# esp01.net
KiCad netlist of a schematic drawn in EAGLE
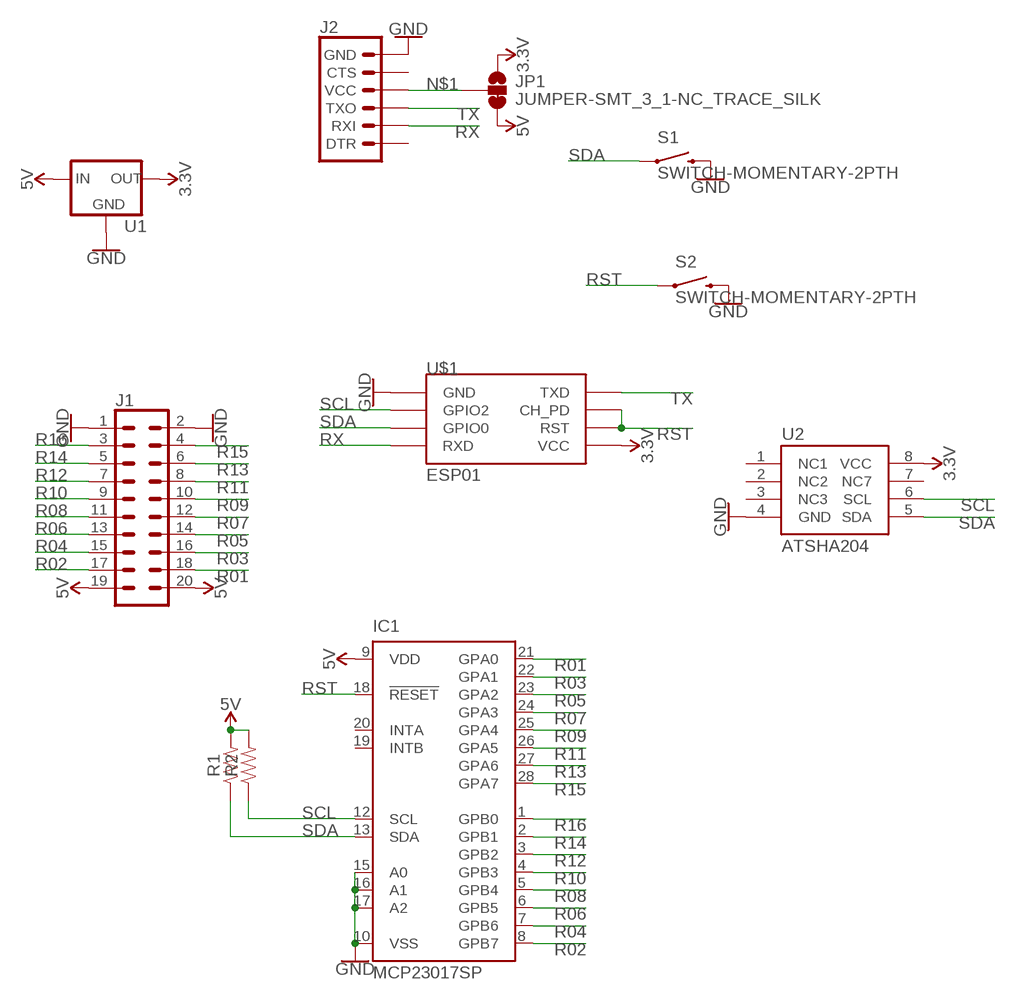
[diagram p0: schematic, sheet 1]

(export (version "E")
  (design (tool "Eeschema 10.0.6"))
  (components
    (comp (ref "IC1")
      (value "MCP23017SP")
      (footprint "eagle-import:DIL28-3")
      (libsource (lib "eagle-import") (part "MCP23017SP"))
    )
    (comp (ref "J1")
      (value "CONN_10X2")
      (footprint "eagle-import:2X10")
      (libsource (lib "eagle-import") (part "CONN_10X2"))
    )
    (comp (ref "J2")
      (value "6_PIN_SERIAL_TARGETLONGPADS")
      (footprint "eagle-import:1X06_LONGPADS")
      (libsource (lib "eagle-import") (part "6_PIN_SERIAL_TARGETLONGPADS"))
    )
    (comp (ref "JP1")
      (value "JUMPER-SMT_3_1-NC_TRACE_SILK")
      (footprint "eagle-import:SMT-JUMPER_3_1-NC_TRACE_SILK")
      (libsource (lib "eagle-import") (part "JUMPER-SMT_3_1-NC_TRACE_SILK"))
    )
    (comp (ref "R1")
      (value "RESISTORAXIAL-0.3")
      (footprint "eagle-import:AXIAL-0.3")
      (libsource (lib "eagle-import") (part "RESISTORAXIAL-0.3"))
    )
    (comp (ref "R2")
      (value "RESISTORAXIAL-0.3")
      (footprint "eagle-import:AXIAL-0.3")
      (libsource (lib "eagle-import") (part "RESISTORAXIAL-0.3"))
    )
    (comp (ref "S1")
      (value "SWITCH-MOMENTARY-2PTH")
      (footprint "eagle-import:TACTILE-PTH")
      (libsource (lib "eagle-import") (part "SWITCH-MOMENTARY-2PTH"))
    )
    (comp (ref "S2")
      (value "SWITCH-MOMENTARY-2PTH")
      (footprint "eagle-import:TACTILE-PTH")
      (libsource (lib "eagle-import") (part "SWITCH-MOMENTARY-2PTH"))
    )
    (comp (ref "U$1")
      (value "ESP01")
      (footprint "eagle-import:ESP01")
      (libsource (lib "eagle-import") (part "ESP01"))
    )
    (comp (ref "U1")
      (value "V_REG_78XXSIDE")
      (footprint "eagle-import:78XXL")
      (libsource (lib "eagle-import") (part "V_REG_78XXSIDE"))
    )
    (comp (ref "U2")
      (value "ATSHA204")
      (footprint "eagle-import:SO08")
      (libsource (lib "eagle-import") (part "ATSHA204_SOIC8"))
    )
  )
  (nets
    (net (code "1") (name "3.3V") (class "Default")
      (node (ref "JP1") (pin "1") (pinfunction "1_1") (pintype "passive"))
      (node (ref "U$1") (pin "VCC") (pinfunction "VCC_VCC") (pintype "bidirectional"))
      (node (ref "U1") (pin "OUT") (pinfunction "OUT_OUT") (pintype "passive"))
      (node (ref "U2") (pin "8") (pinfunction "VCC_8") (pintype "power_in"))
    )
    (net (code "2") (name "5V") (class "Default")
      (node (ref "IC1") (pin "9") (pinfunction "VDD_9") (pintype "power_in"))
      (node (ref "J1") (pin "19") (pinfunction "19_19") (pintype "passive"))
      (node (ref "J1") (pin "20") (pinfunction "20_20") (pintype "passive"))
      (node (ref "JP1") (pin "3") (pinfunction "3_3") (pintype "passive"))
      (node (ref "R1") (pin "P$2") (pinfunction "2_P$2") (pintype "passive"))
      (node (ref "R2") (pin "P$2") (pinfunction "2_P$2") (pintype "passive"))
      (node (ref "U1") (pin "IN") (pinfunction "IN_IN") (pintype "input"))
    )
    (net (code "3") (name "GND") (class "Default")
      (node (ref "IC1") (pin "10") (pinfunction "VSS_10") (pintype "power_in"))
      (node (ref "IC1") (pin "15") (pinfunction "A0_15") (pintype "input"))
      (node (ref "IC1") (pin "16") (pinfunction "A1_16") (pintype "input"))
      (node (ref "IC1") (pin "17") (pinfunction "A2_17") (pintype "input"))
      (node (ref "J1") (pin "1") (pinfunction "1_1") (pintype "passive"))
      (node (ref "J1") (pin "2") (pinfunction "2_2") (pintype "passive"))
      (node (ref "J2") (pin "6") (pinfunction "GND_6") (pintype "passive"))
      (node (ref "S1") (pin "3") (pinfunction "2_3") (pintype "passive"))
      (node (ref "S1") (pin "4") (pinfunction "2_4") (pintype "passive"))
      (node (ref "S2") (pin "3") (pinfunction "2_3") (pintype "passive"))
      (node (ref "S2") (pin "4") (pinfunction "2_4") (pintype "passive"))
      (node (ref "U$1") (pin "GND") (pinfunction "GND_GND") (pintype "bidirectional"))
      (node (ref "U1") (pin "GND") (pinfunction "GND_GND") (pintype "input"))
      (node (ref "U2") (pin "4") (pinfunction "GND_4") (pintype "power_in"))
    )
    (net (code "4") (name "N$1") (class "Default")
      (node (ref "J2") (pin "4") (pinfunction "VCC_4") (pintype "passive"))
      (node (ref "JP1") (pin "2") (pinfunction "2_2") (pintype "passive"))
    )
    (net (code "5") (name "R01") (class "Default")
      (node (ref "IC1") (pin "21") (pinfunction "GPA0_21") (pintype "bidirectional"))
      (node (ref "J1") (pin "18") (pinfunction "18_18") (pintype "passive"))
    )
    (net (code "6") (name "R02") (class "Default")
      (node (ref "IC1") (pin "8") (pinfunction "GPB7_8") (pintype "bidirectional"))
      (node (ref "J1") (pin "17") (pinfunction "17_17") (pintype "passive"))
    )
    (net (code "7") (name "R03") (class "Default")
      (node (ref "IC1") (pin "22") (pinfunction "GPA1_22") (pintype "bidirectional"))
      (node (ref "J1") (pin "16") (pinfunction "16_16") (pintype "passive"))
    )
    (net (code "8") (name "R04") (class "Default")
      (node (ref "IC1") (pin "7") (pinfunction "GPB6_7") (pintype "bidirectional"))
      (node (ref "J1") (pin "15") (pinfunction "15_15") (pintype "passive"))
    )
    (net (code "9") (name "R05") (class "Default")
      (node (ref "IC1") (pin "23") (pinfunction "GPA2_23") (pintype "bidirectional"))
      (node (ref "J1") (pin "14") (pinfunction "14_14") (pintype "passive"))
    )
    (net (code "10") (name "R06") (class "Default")
      (node (ref "IC1") (pin "6") (pinfunction "GPB5_6") (pintype "bidirectional"))
      (node (ref "J1") (pin "13") (pinfunction "13_13") (pintype "passive"))
    )
    (net (code "11") (name "R07") (class "Default")
      (node (ref "IC1") (pin "24") (pinfunction "GPA3_24") (pintype "bidirectional"))
      (node (ref "J1") (pin "12") (pinfunction "12_12") (pintype "passive"))
    )
    (net (code "12") (name "R08") (class "Default")
      (node (ref "IC1") (pin "5") (pinfunction "GPB4_5") (pintype "bidirectional"))
      (node (ref "J1") (pin "11") (pinfunction "11_11") (pintype "passive"))
    )
    (net (code "13") (name "R09") (class "Default")
      (node (ref "IC1") (pin "25") (pinfunction "GPA4_25") (pintype "bidirectional"))
      (node (ref "J1") (pin "10") (pinfunction "10_10") (pintype "passive"))
    )
    (net (code "14") (name "R10") (class "Default")
      (node (ref "IC1") (pin "4") (pinfunction "GPB3_4") (pintype "bidirectional"))
      (node (ref "J1") (pin "9") (pinfunction "9_9") (pintype "passive"))
    )
    (net (code "15") (name "R11") (class "Default")
      (node (ref "IC1") (pin "26") (pinfunction "GPA5_26") (pintype "bidirectional"))
      (node (ref "J1") (pin "8") (pinfunction "8_8") (pintype "passive"))
    )
    (net (code "16") (name "R12") (class "Default")
      (node (ref "IC1") (pin "3") (pinfunction "GPB2_3") (pintype "bidirectional"))
      (node (ref "J1") (pin "7") (pinfunction "7_7") (pintype "passive"))
    )
    (net (code "17") (name "R13") (class "Default")
      (node (ref "IC1") (pin "27") (pinfunction "GPA6_27") (pintype "bidirectional"))
      (node (ref "J1") (pin "6") (pinfunction "6_6") (pintype "passive"))
    )
    (net (code "18") (name "R14") (class "Default")
      (node (ref "IC1") (pin "2") (pinfunction "GPB1_2") (pintype "bidirectional"))
      (node (ref "J1") (pin "5") (pinfunction "5_5") (pintype "passive"))
    )
    (net (code "19") (name "R15") (class "Default")
      (node (ref "IC1") (pin "28") (pinfunction "GPA7_28") (pintype "bidirectional"))
      (node (ref "J1") (pin "4") (pinfunction "4_4") (pintype "passive"))
    )
    (net (code "20") (name "R16") (class "Default")
      (node (ref "IC1") (pin "1") (pinfunction "GPB0_1") (pintype "bidirectional"))
      (node (ref "J1") (pin "3") (pinfunction "3_3") (pintype "passive"))
    )
    (net (code "21") (name "RST") (class "Default")
      (node (ref "IC1") (pin "18") (pinfunction "~{RESET}_18") (pintype "input"))
      (node (ref "S2") (pin "1") (pinfunction "1_1") (pintype "passive"))
      (node (ref "S2") (pin "2") (pinfunction "1_2") (pintype "passive"))
      (node (ref "U$1") (pin "CH_PD") (pinfunction "CH_PD_CH_PD") (pintype "bidirectional"))
      (node (ref "U$1") (pin "RST") (pinfunction "RST_RST") (pintype "bidirectional"))
    )
    (net (code "22") (name "RX") (class "Default")
      (node (ref "J2") (pin "2") (pinfunction "RXI_2") (pintype "passive"))
      (node (ref "U$1") (pin "RX") (pinfunction "RXD_RX") (pintype "bidirectional"))
    )
    (net (code "23") (name "SCL") (class "Default")
      (node (ref "IC1") (pin "12") (pinfunction "SCL_12") (pintype "input"))
      (node (ref "R2") (pin "P$1") (pinfunction "1_P$1") (pintype "passive"))
      (node (ref "U$1") (pin "GPIO2") (pinfunction "GPIO2_GPIO2") (pintype "bidirectional"))
      (node (ref "U2") (pin "6") (pinfunction "SCL_6") (pintype "bidirectional"))
    )
    (net (code "24") (name "SDA") (class "Default")
      (node (ref "IC1") (pin "13") (pinfunction "SDA_13") (pintype "bidirectional"))
      (node (ref "R1") (pin "P$1") (pinfunction "1_P$1") (pintype "passive"))
      (node (ref "S1") (pin "1") (pinfunction "1_1") (pintype "passive"))
      (node (ref "S1") (pin "2") (pinfunction "1_2") (pintype "passive"))
      (node (ref "U$1") (pin "GPIO0") (pinfunction "GPIO0_GPIO0") (pintype "bidirectional"))
      (node (ref "U2") (pin "5") (pinfunction "SDA_5") (pintype "bidirectional"))
    )
    (net (code "25") (name "TX") (class "Default")
      (node (ref "J2") (pin "3") (pinfunction "TXO_3") (pintype "passive"))
      (node (ref "U$1") (pin "TX") (pinfunction "TXD_TX") (pintype "bidirectional"))
    )
    (net (code "26") (name "unconnected-(IC1-INTA-Pad20)") (class "Default")
      (node (ref "IC1") (pin "20") (pinfunction "INTA_20") (pintype "output"))
    )
    (net (code "27") (name "unconnected-(IC1-INTB-Pad19)") (class "Default")
      (node (ref "IC1") (pin "19") (pinfunction "INTB_19") (pintype "output"))
    )
    (net (code "28") (name "unconnected-(J2-CTS-Pad5)") (class "Default")
      (node (ref "J2") (pin "5") (pinfunction "CTS_5") (pintype "passive"))
    )
    (net (code "29") (name "unconnected-(J2-DTR-Pad1)") (class "Default")
      (node (ref "J2") (pin "1") (pinfunction "DTR_1") (pintype "passive"))
    )
    (net (code "30") (name "unconnected-(U2-NC1-Pad1)") (class "Default")
      (node (ref "U2") (pin "1") (pinfunction "NC1_1") (pintype "no_connect"))
    )
    (net (code "31") (name "unconnected-(U2-NC2-Pad2)") (class "Default")
      (node (ref "U2") (pin "2") (pinfunction "NC2_2") (pintype "no_connect"))
    )
    (net (code "32") (name "unconnected-(U2-NC3-Pad3)") (class "Default")
      (node (ref "U2") (pin "3") (pinfunction "NC3_3") (pintype "no_connect"))
    )
    (net (code "33") (name "unconnected-(U2-NC7-Pad7)") (class "Default")
      (node (ref "U2") (pin "7") (pinfunction "NC7_7") (pintype "no_connect"))
    )
  )
)
